# vapeduino_v0001.net
KiCad netlist of a schematic drawn in EAGLE
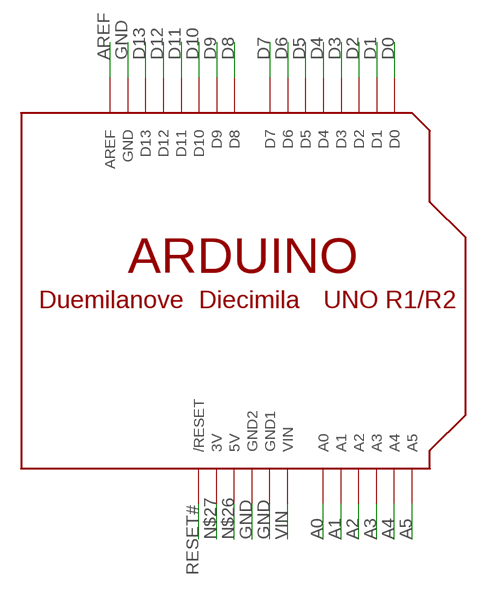
[diagram p0: schematic, sheet 1]
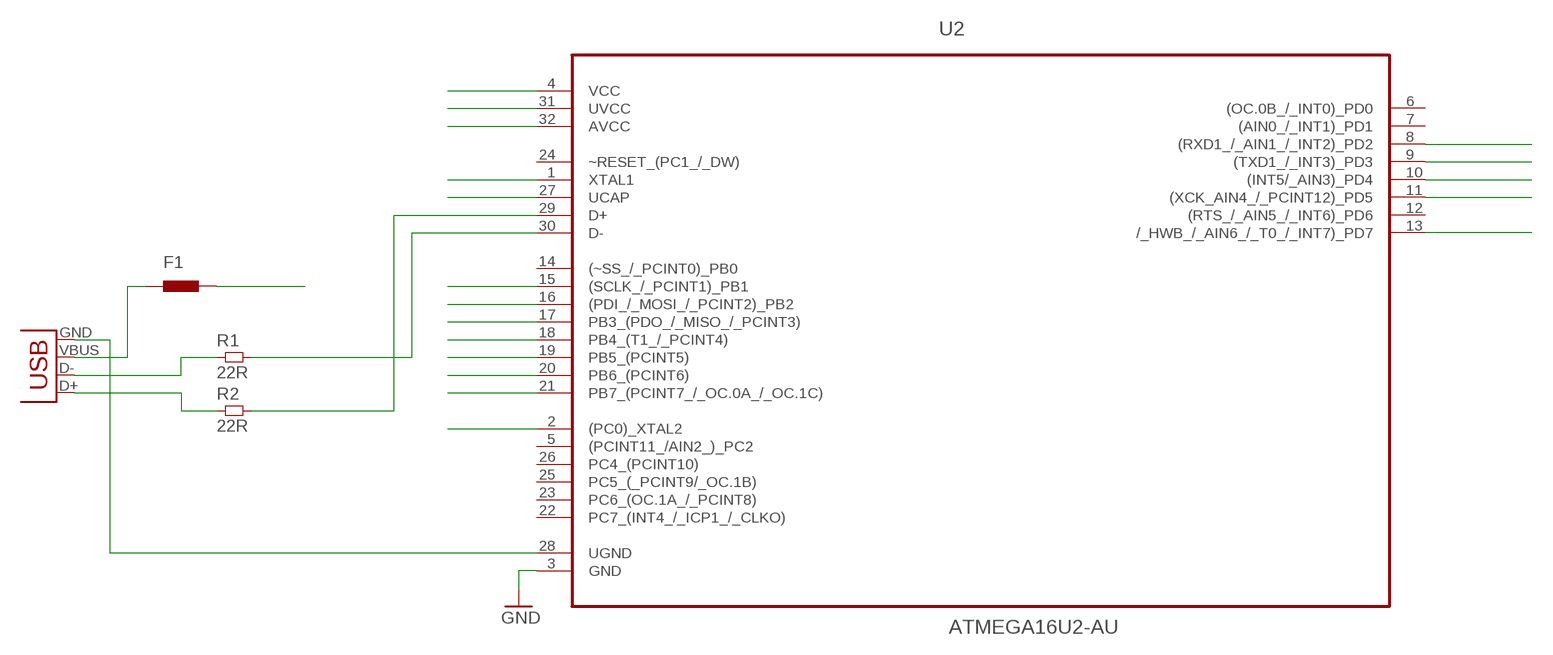
[diagram p1: schematic, sheet 5]
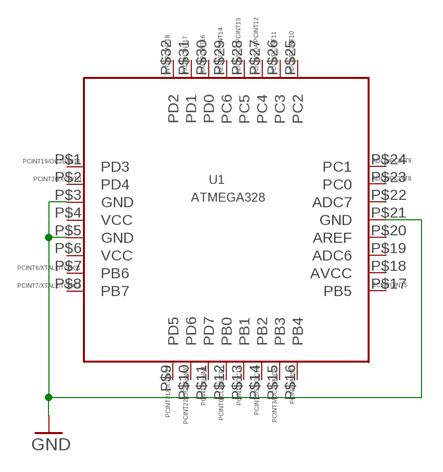
[diagram p2: schematic, sheet 6]

(export (version "E")
  (design (tool "Eeschema 10.0.6"))
  (components
    (comp (ref "F1")
      (value "RES_FUSE")
      (footprint "eagle-import:1812")
      (libsource (lib "eagle-import") (part "RES_FUSE"))
    )
    (comp (ref "JP2")
      (value "USB-B")
      (footprint "eagle-import:USB-B-PTH")
      (libsource (lib "eagle-import") (part "USBPTH"))
    )
    (comp (ref "R1")
      (value "22R")
      (footprint "eagle-import:0603L3")
      (libsource (lib "eagle-import") (part "RES0603L3"))
    )
    (comp (ref "R2")
      (value "22R")
      (footprint "eagle-import:0603L3")
      (libsource (lib "eagle-import") (part "RES0603L3"))
    )
    (comp (ref "U2")
      (value "ATMEGA16U2-AU")
      (footprint "eagle-import:QFP80P900X900X120-32N")
      (libsource (lib "eagle-import") (part "ATMEGA16U2-AU"))
    )
    (comp (ref "U$1")
      (value "ARDUINOUNO")
      (footprint "eagle-import:ARDUINO")
      (libsource (lib "eagle-import") (part "ARDUINOUNO"))
    )
    (comp (ref "U1")
      (value "ATMEGA328")
      (footprint "eagle-import:QFN32")
      (libsource (lib "eagle-import") (part "ATMEGA328"))
    )
  )
  (nets
    (net (code "1") (name "A0") (class "Default")
      (node (ref "U$1") (pin "A0") (pinfunction "A0_A0") (pintype "bidirectional"))
    )
    (net (code "2") (name "A1") (class "Default")
      (node (ref "U$1") (pin "A1") (pinfunction "A1_A1") (pintype "bidirectional"))
    )
    (net (code "3") (name "A2") (class "Default")
      (node (ref "U$1") (pin "A2") (pinfunction "A2_A2") (pintype "bidirectional"))
    )
    (net (code "4") (name "A3") (class "Default")
      (node (ref "U$1") (pin "A3") (pinfunction "A3_A3") (pintype "bidirectional"))
    )
    (net (code "5") (name "A4") (class "Default")
      (node (ref "U$1") (pin "A4") (pinfunction "A4_A4") (pintype "bidirectional"))
    )
    (net (code "6") (name "A5") (class "Default")
      (node (ref "U$1") (pin "A5") (pinfunction "A5_A5") (pintype "bidirectional"))
    )
    (net (code "7") (name "AREF") (class "Default")
      (node (ref "U$1") (pin "AREF") (pinfunction "AREF_AREF") (pintype "bidirectional"))
    )
    (net (code "8") (name "D0") (class "Default")
      (node (ref "U$1") (pin "D0") (pinfunction "D0_D0") (pintype "bidirectional"))
    )
    (net (code "9") (name "D1") (class "Default")
      (node (ref "U$1") (pin "D1") (pinfunction "D1_D1") (pintype "bidirectional"))
    )
    (net (code "10") (name "D2") (class "Default")
      (node (ref "U$1") (pin "D2") (pinfunction "D2_D2") (pintype "bidirectional"))
    )
    (net (code "11") (name "D3") (class "Default")
      (node (ref "U$1") (pin "D3") (pinfunction "D3_D3") (pintype "bidirectional"))
    )
    (net (code "12") (name "D4") (class "Default")
      (node (ref "U$1") (pin "D4") (pinfunction "D4_D4") (pintype "bidirectional"))
    )
    (net (code "13") (name "D5") (class "Default")
      (node (ref "U$1") (pin "D5") (pinfunction "D5_D5") (pintype "bidirectional"))
    )
    (net (code "14") (name "D6") (class "Default")
      (node (ref "U$1") (pin "D6") (pinfunction "D6_D6") (pintype "bidirectional"))
    )
    (net (code "15") (name "D7") (class "Default")
      (node (ref "U$1") (pin "D7") (pinfunction "D7_D7") (pintype "bidirectional"))
    )
    (net (code "16") (name "D8") (class "Default")
      (node (ref "U$1") (pin "D8") (pinfunction "D8_D8") (pintype "bidirectional"))
    )
    (net (code "17") (name "D9") (class "Default")
      (node (ref "U$1") (pin "D9") (pinfunction "D9_D9") (pintype "bidirectional"))
    )
    (net (code "18") (name "D10") (class "Default")
      (node (ref "U$1") (pin "D10") (pinfunction "D10_D10") (pintype "bidirectional"))
    )
    (net (code "19") (name "D11") (class "Default")
      (node (ref "U$1") (pin "D11") (pinfunction "D11_D11") (pintype "bidirectional"))
    )
    (net (code "20") (name "D12") (class "Default")
      (node (ref "U$1") (pin "D12") (pinfunction "D12_D12") (pintype "bidirectional"))
    )
    (net (code "21") (name "D13") (class "Default")
      (node (ref "U$1") (pin "D13") (pinfunction "D13_D13") (pintype "bidirectional"))
    )
    (net (code "22") (name "GND") (class "Default")
      (node (ref "U$1") (pin "GND") (pinfunction "GND_GND") (pintype "power_in"))
      (node (ref "U$1") (pin "GND1") (pinfunction "GND1_GND1") (pintype "power_in"))
      (node (ref "U$1") (pin "GND2") (pinfunction "GND2_GND2") (pintype "power_in"))
      (node (ref "U1") (pin "P$21") (pinfunction "GND_P$21") (pintype "bidirectional"))
      (node (ref "U1") (pin "P$3") (pinfunction "GND_P$3") (pintype "bidirectional"))
      (node (ref "U1") (pin "P$5") (pinfunction "GND_P$5") (pintype "bidirectional"))
      (node (ref "U2") (pin "3") (pinfunction "GND_3") (pintype "passive"))
    )
    (net (code "23") (name "N$26") (class "Default")
      (node (ref "U$1") (pin "5V") (pinfunction "5V_5V") (pintype "power_in"))
    )
    (net (code "24") (name "N$27") (class "Default")
      (node (ref "U$1") (pin "3V") (pinfunction "3V_3V") (pintype "power_in"))
    )
    (net (code "25") (name "Net-(F1-P$1)") (class "Default")
      (node (ref "F1") (pin "1") (pinfunction "P$1_1") (pintype "bidirectional"))
      (node (ref "JP2") (pin "VBUS") (pinfunction "VBUS_VBUS") (pintype "bidirectional"))
    )
    (net (code "26") (name "Net-(R1-1)") (class "Default")
      (node (ref "JP2") (pin "D-") (pinfunction "D-_D-") (pintype "bidirectional"))
      (node (ref "R1") (pin "P$1") (pinfunction "1_P$1") (pintype "bidirectional"))
    )
    (net (code "27") (name "Net-(R1-2)") (class "Default")
      (node (ref "R1") (pin "P$2") (pinfunction "2_P$2") (pintype "bidirectional"))
      (node (ref "U2") (pin "30") (pinfunction "D-_30") (pintype "passive"))
    )
    (net (code "28") (name "Net-(R2-1)") (class "Default")
      (node (ref "JP2") (pin "D+") (pinfunction "D+_D+") (pintype "bidirectional"))
      (node (ref "R2") (pin "P$1") (pinfunction "1_P$1") (pintype "bidirectional"))
    )
    (net (code "29") (name "Net-(R2-2)") (class "Default")
      (node (ref "R2") (pin "P$2") (pinfunction "2_P$2") (pintype "bidirectional"))
      (node (ref "U2") (pin "29") (pinfunction "D+_29") (pintype "passive"))
    )
    (net (code "30") (name "Net-(U2-UGND)") (class "Default")
      (node (ref "JP2") (pin "GND") (pinfunction "GND_GND") (pintype "bidirectional"))
      (node (ref "U2") (pin "28") (pinfunction "UGND_28") (pintype "passive"))
    )
    (net (code "31") (name "RESET#") (class "Default")
      (node (ref "U$1") (pin "RESET") (pinfunction "/RESET_RESET") (pintype "bidirectional"))
    )
    (net (code "32") (name "VIN") (class "Default")
      (node (ref "U$1") (pin "VIN") (pinfunction "VIN_VIN") (pintype "power_in"))
    )
    (net (code "33") (name "unconnected-(F1-P$2-Pad2)") (class "Default")
      (node (ref "F1") (pin "2") (pinfunction "P$2_2") (pintype "bidirectional"))
    )
    (net (code "34") (name "unconnected-(U1-ADC6-PadP$19)") (class "Default")
      (node (ref "U1") (pin "P$19") (pinfunction "ADC6_P$19") (pintype "bidirectional"))
    )
    (net (code "35") (name "unconnected-(U1-ADC7-PadP$22)") (class "Default")
      (node (ref "U1") (pin "P$22") (pinfunction "ADC7_P$22") (pintype "bidirectional"))
    )
    (net (code "36") (name "unconnected-(U1-AREF-PadP$20)") (class "Default")
      (node (ref "U1") (pin "P$20") (pinfunction "AREF_P$20") (pintype "bidirectional"))
    )
    (net (code "37") (name "unconnected-(U1-AVCC-PadP$18)") (class "Default")
      (node (ref "U1") (pin "P$18") (pinfunction "AVCC_P$18") (pintype "bidirectional"))
    )
    (net (code "38") (name "unconnected-(U1-PB0-PadP$12)") (class "Default")
      (node (ref "U1") (pin "P$12") (pinfunction "PB0_P$12") (pintype "bidirectional"))
    )
    (net (code "39") (name "unconnected-(U1-PB1-PadP$13)") (class "Default")
      (node (ref "U1") (pin "P$13") (pinfunction "PB1_P$13") (pintype "bidirectional"))
    )
    (net (code "40") (name "unconnected-(U1-PB2-PadP$14)") (class "Default")
      (node (ref "U1") (pin "P$14") (pinfunction "PB2_P$14") (pintype "bidirectional"))
    )
    (net (code "41") (name "unconnected-(U1-PB3-PadP$15)") (class "Default")
      (node (ref "U1") (pin "P$15") (pinfunction "PB3_P$15") (pintype "bidirectional"))
    )
    (net (code "42") (name "unconnected-(U1-PB4-PadP$16)") (class "Default")
      (node (ref "U1") (pin "P$16") (pinfunction "PB4_P$16") (pintype "bidirectional"))
    )
    (net (code "43") (name "unconnected-(U1-PB5-PadP$17)") (class "Default")
      (node (ref "U1") (pin "P$17") (pinfunction "PB5_P$17") (pintype "bidirectional"))
    )
    (net (code "44") (name "unconnected-(U1-PB6-PadP$7)") (class "Default")
      (node (ref "U1") (pin "P$7") (pinfunction "PB6_P$7") (pintype "bidirectional"))
    )
    (net (code "45") (name "unconnected-(U1-PB7-PadP$8)") (class "Default")
      (node (ref "U1") (pin "P$8") (pinfunction "PB7_P$8") (pintype "bidirectional"))
    )
    (net (code "46") (name "unconnected-(U1-PC0-PadP$23)") (class "Default")
      (node (ref "U1") (pin "P$23") (pinfunction "PC0_P$23") (pintype "bidirectional"))
    )
    (net (code "47") (name "unconnected-(U1-PC1-PadP$24)") (class "Default")
      (node (ref "U1") (pin "P$24") (pinfunction "PC1_P$24") (pintype "bidirectional"))
    )
    (net (code "48") (name "unconnected-(U1-PC2-PadP$25)") (class "Default")
      (node (ref "U1") (pin "P$25") (pinfunction "PC2_P$25") (pintype "bidirectional"))
    )
    (net (code "49") (name "unconnected-(U1-PC3-PadP$26)") (class "Default")
      (node (ref "U1") (pin "P$26") (pinfunction "PC3_P$26") (pintype "bidirectional"))
    )
    (net (code "50") (name "unconnected-(U1-PC4-PadP$27)") (class "Default")
      (node (ref "U1") (pin "P$27") (pinfunction "PC4_P$27") (pintype "bidirectional"))
    )
    (net (code "51") (name "unconnected-(U1-PC5-PadP$28)") (class "Default")
      (node (ref "U1") (pin "P$28") (pinfunction "PC5_P$28") (pintype "bidirectional"))
    )
    (net (code "52") (name "unconnected-(U1-PC6-PadP$29)") (class "Default")
      (node (ref "U1") (pin "P$29") (pinfunction "PC6_P$29") (pintype "bidirectional"))
    )
    (net (code "53") (name "unconnected-(U1-PD0-PadP$30)") (class "Default")
      (node (ref "U1") (pin "P$30") (pinfunction "PD0_P$30") (pintype "bidirectional"))
    )
    (net (code "54") (name "unconnected-(U1-PD1-PadP$31)") (class "Default")
      (node (ref "U1") (pin "P$31") (pinfunction "PD1_P$31") (pintype "bidirectional"))
    )
    (net (code "55") (name "unconnected-(U1-PD2-PadP$32)") (class "Default")
      (node (ref "U1") (pin "P$32") (pinfunction "PD2_P$32") (pintype "bidirectional"))
    )
    (net (code "56") (name "unconnected-(U1-PD3-PadP$1)") (class "Default")
      (node (ref "U1") (pin "P$1") (pinfunction "PD3_P$1") (pintype "bidirectional"))
    )
    (net (code "57") (name "unconnected-(U1-PD4-PadP$2)") (class "Default")
      (node (ref "U1") (pin "P$2") (pinfunction "PD4_P$2") (pintype "bidirectional"))
    )
    (net (code "58") (name "unconnected-(U1-PD5-PadP$9)") (class "Default")
      (node (ref "U1") (pin "P$9") (pinfunction "PD5_P$9") (pintype "bidirectional"))
    )
    (net (code "59") (name "unconnected-(U1-PD6-PadP$10)") (class "Default")
      (node (ref "U1") (pin "P$10") (pinfunction "PD6_P$10") (pintype "bidirectional"))
    )
    (net (code "60") (name "unconnected-(U1-PD7-PadP$11)") (class "Default")
      (node (ref "U1") (pin "P$11") (pinfunction "PD7_P$11") (pintype "bidirectional"))
    )
    (net (code "61") (name "unconnected-(U1-VCC-PadP$4)") (class "Default")
      (node (ref "U1") (pin "P$4") (pinfunction "VCC_P$4") (pintype "bidirectional"))
    )
    (net (code "62") (name "unconnected-(U1-VCC-PadP$6)") (class "Default")
      (node (ref "U1") (pin "P$6") (pinfunction "VCC_P$6") (pintype "bidirectional"))
    )
    (net (code "63") (name "unconnected-(U2-(AIN0_{slash}_INT1)_PD1-Pad7)") (class "Default")
      (node (ref "U2") (pin "7") (pinfunction "(AIN0_/_INT1)_PD1_7") (pintype "bidirectional"))
    )
    (net (code "64") (name "unconnected-(U2-(INT5{slash}_AIN3)_PD4-Pad10)") (class "Default")
      (node (ref "U2") (pin "10") (pinfunction "(INT5/_AIN3)_PD4_10") (pintype "bidirectional"))
    )
    (net (code "65") (name "unconnected-(U2-(OC.0B_{slash}_INT0)_PD0-Pad6)") (class "Default")
      (node (ref "U2") (pin "6") (pinfunction "(OC.0B_/_INT0)_PD0_6") (pintype "bidirectional"))
    )
    (net (code "66") (name "unconnected-(U2-(PC0)_XTAL2-Pad2)") (class "Default")
      (node (ref "U2") (pin "2") (pinfunction "(PC0)_XTAL2_2") (pintype "output"))
    )
    (net (code "67") (name "unconnected-(U2-(PCINT11_{slash}AIN2_)_PC2-Pad5)") (class "Default")
      (node (ref "U2") (pin "5") (pinfunction "(PCINT11_/AIN2_)_PC2_5") (pintype "bidirectional"))
    )
    (net (code "68") (name "unconnected-(U2-(PDI_{slash}_MOSI_{slash}_PCINT2)_PB2-Pad16)") (class "Default")
      (node (ref "U2") (pin "16") (pinfunction "(PDI_/_MOSI_/_PCINT2)_PB2_16") (pintype "bidirectional"))
    )
    (net (code "69") (name "unconnected-(U2-(RTS_{slash}_AIN5_{slash}_INT6)_PD6-Pad12)") (class "Default")
      (node (ref "U2") (pin "12") (pinfunction "(RTS_/_AIN5_/_INT6)_PD6_12") (pintype "bidirectional"))
    )
    (net (code "70") (name "unconnected-(U2-(RXD1_{slash}_AIN1_{slash}_INT2)_PD2-Pad8)") (class "Default")
      (node (ref "U2") (pin "8") (pinfunction "(RXD1_/_AIN1_/_INT2)_PD2_8") (pintype "bidirectional"))
    )
    (net (code "71") (name "unconnected-(U2-(SCLK_{slash}_PCINT1)_PB1-Pad15)") (class "Default")
      (node (ref "U2") (pin "15") (pinfunction "(SCLK_/_PCINT1)_PB1_15") (pintype "bidirectional"))
    )
    (net (code "72") (name "unconnected-(U2-(TXD1_{slash}_INT3)_PD3-Pad9)") (class "Default")
      (node (ref "U2") (pin "9") (pinfunction "(TXD1_/_INT3)_PD3_9") (pintype "bidirectional"))
    )
    (net (code "73") (name "unconnected-(U2-(XCK_AIN4_{slash}_PCINT12)_PD5-Pad11)") (class "Default")
      (node (ref "U2") (pin "11") (pinfunction "(XCK_AIN4_/_PCINT12)_PD5_11") (pintype "bidirectional"))
    )
    (net (code "74") (name "unconnected-(U2-(~{SS_{slash}_PCINT0})_PB0-Pad14)") (class "Default")
      (node (ref "U2") (pin "14") (pinfunction "(~{SS_/_PCINT0})_PB0_14") (pintype "bidirectional"))
    )
    (net (code "75") (name "unconnected-(U2-AVCC-Pad32)") (class "Default")
      (node (ref "U2") (pin "32") (pinfunction "AVCC_32") (pintype "power_in"))
    )
    (net (code "76") (name "unconnected-(U2-PB3_(PDO_{slash}_MISO_{slash}_PCINT3)-Pad17)") (class "Default")
      (node (ref "U2") (pin "17") (pinfunction "PB3_(PDO_/_MISO_/_PCINT3)_17") (pintype "bidirectional"))
    )
    (net (code "77") (name "unconnected-(U2-PB4_(T1_{slash}_PCINT4)-Pad18)") (class "Default")
      (node (ref "U2") (pin "18") (pinfunction "PB4_(T1_/_PCINT4)_18") (pintype "bidirectional"))
    )
    (net (code "78") (name "unconnected-(U2-PB5_(PCINT5)-Pad19)") (class "Default")
      (node (ref "U2") (pin "19") (pinfunction "PB5_(PCINT5)_19") (pintype "bidirectional"))
    )
    (net (code "79") (name "unconnected-(U2-PB6_(PCINT6)-Pad20)") (class "Default")
      (node (ref "U2") (pin "20") (pinfunction "PB6_(PCINT6)_20") (pintype "bidirectional"))
    )
    (net (code "80") (name "unconnected-(U2-PB7_(PCINT7_{slash}_OC.0A_{slash}_OC.1C)-Pad21)") (class "Default")
      (node (ref "U2") (pin "21") (pinfunction "PB7_(PCINT7_/_OC.0A_/_OC.1C)_21") (pintype "bidirectional"))
    )
    (net (code "81") (name "unconnected-(U2-PC4_(PCINT10)-Pad26)") (class "Default")
      (node (ref "U2") (pin "26") (pinfunction "PC4_(PCINT10)_26") (pintype "bidirectional"))
    )
    (net (code "82") (name "unconnected-(U2-PC5_(_PCINT9{slash}_OC.1B)-Pad25)") (class "Default")
      (node (ref "U2") (pin "25") (pinfunction "PC5_(_PCINT9/_OC.1B)_25") (pintype "bidirectional"))
    )
    (net (code "83") (name "unconnected-(U2-PC6_(OC.1A_{slash}_PCINT8)-Pad23)") (class "Default")
      (node (ref "U2") (pin "23") (pinfunction "PC6_(OC.1A_/_PCINT8)_23") (pintype "bidirectional"))
    )
    (net (code "84") (name "unconnected-(U2-PC7_(INT4_{slash}_ICP1_{slash}_CLKO)-Pad22)") (class "Default")
      (node (ref "U2") (pin "22") (pinfunction "PC7_(INT4_/_ICP1_/_CLKO)_22") (pintype "bidirectional"))
    )
    (net (code "85") (name "unconnected-(U2-UCAP-Pad27)") (class "Default")
      (node (ref "U2") (pin "27") (pinfunction "UCAP_27") (pintype "passive"))
    )
    (net (code "86") (name "unconnected-(U2-UVCC-Pad31)") (class "Default")
      (node (ref "U2") (pin "31") (pinfunction "UVCC_31") (pintype "power_in"))
    )
    (net (code "87") (name "unconnected-(U2-VCC-Pad4)") (class "Default")
      (node (ref "U2") (pin "4") (pinfunction "VCC_4") (pintype "power_in"))
    )
    (net (code "88") (name "unconnected-(U2-XTAL1-Pad1)") (class "Default")
      (node (ref "U2") (pin "1") (pinfunction "XTAL1_1") (pintype "input"))
    )
    (net (code "89") (name "unconnected-(U2-{slash}_HWB_{slash}_AIN6_{slash}_T0_{slash}_INT7)_PD7-Pad13)") (class "Default")
      (node (ref "U2") (pin "13") (pinfunction "/_HWB_/_AIN6_/_T0_/_INT7)_PD7_13") (pintype "bidirectional"))
    )
    (net (code "90") (name "unconnected-(U2-~{RESET_(PC1_{slash}_DW})-Pad24)") (class "Default")
      (node (ref "U2") (pin "24") (pinfunction "~{RESET_(PC1_/_DW})_24") (pintype "input"))
    )
  )
)
